# JTAG_UART.net
KiCad netlist of a schematic drawn in Altium Designer
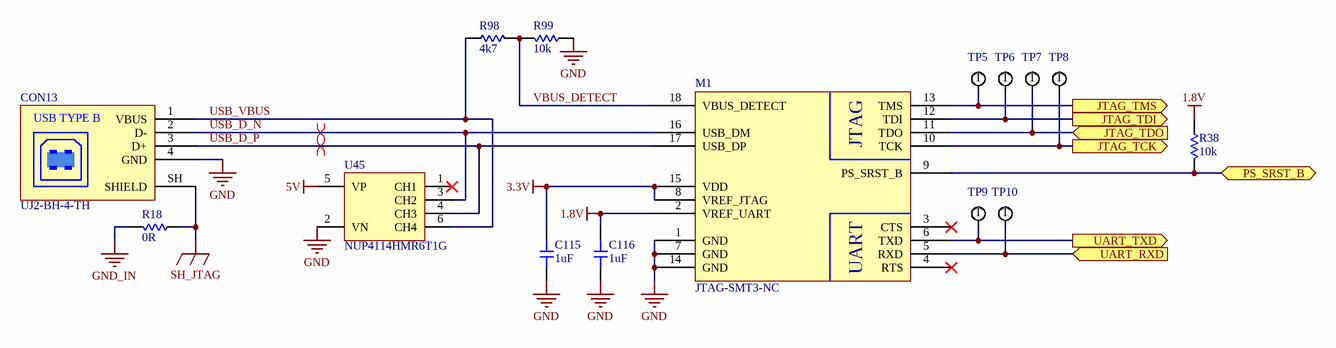
[diagram p0: JTAG_UART.SchDoc]

(export (version "E")
  (design (tool "Eeschema 10.0.6"))
  (components
    (comp (ref "C115")
      (value "1uF")
      (footprint "0603-CAP")
      (description "Capacitor")
      (libsource (lib "AMDC") (part "Capacitor"))
    )
    (comp (ref "C116")
      (value "1uF")
      (footprint "0603-CAP")
      (description "Capacitor")
      (libsource (lib "AMDC") (part "Capacitor"))
    )
    (comp (ref "CON13")
      (value "UJ2-BH-4-TH")
      (footprint "UJ2-BH-4-TH")
      (description "CONN RCPT USB2.0 TYPEB 4POS R/A")
      (libsource (lib "AMDC") (part "UJ2-BH-4-TH"))
    )
    (comp (ref "M1")
      (value "JTAG-SMT3-NC")
      (footprint "JTAG-SMT3-NC")
      (description "JTAG-SMT3-NC: SURFACE-MOUNT PROG")
      (libsource (lib "AMDC") (part "JTAG-SMT3-NC"))
    )
    (comp (ref "R18")
      (value "0R")
      (footprint "1206-RES")
      (description "Resistor")
      (libsource (lib "AMDC") (part "Resistor"))
    )
    (comp (ref "R38")
      (value "10k")
      (footprint "0603-RES")
      (description "Resistor")
      (libsource (lib "AMDC") (part "Resistor"))
    )
    (comp (ref "R98")
      (value "4k7")
      (footprint "0603-RES")
      (description "Resistor")
      (libsource (lib "AMDC") (part "Resistor"))
    )
    (comp (ref "R99")
      (value "10k")
      (footprint "0603-RES")
      (description "Resistor")
      (libsource (lib "AMDC") (part "Resistor"))
    )
    (comp (ref "TP5") (value "Test Point") (footprint "TP-125") (libsource (lib "AMDC") (part "Test Point")))
    (comp (ref "TP6") (value "Test Point") (footprint "TP-125") (libsource (lib "AMDC") (part "Test Point")))
    (comp (ref "TP7") (value "Test Point") (footprint "TP-125") (libsource (lib "AMDC") (part "Test Point")))
    (comp (ref "TP8") (value "Test Point") (footprint "TP-125") (libsource (lib "AMDC") (part "Test Point")))
    (comp (ref "TP9") (value "Test Point") (footprint "TP-125") (libsource (lib "AMDC") (part "Test Point")))
    (comp (ref "TP10") (value "Test Point") (footprint "TP-125") (libsource (lib "AMDC") (part "Test Point")))
    (comp (ref "U45")
      (value "NUP4114HMR6T1G")
      (footprint "TSOP95P280X110-6N")
      (description "TVS DIODE 5.5V 10V 6TSOP")
      (libsource (lib "AMDC") (part "NUP4114HMR6T1G"))
    )
  )
  (nets
    (net (code "1") (name "/JTAG_TCK") (class "Default")
      (node (ref "M1") (pin "10") (pinfunction "TCK_10") (pintype "passive"))
      (node (ref "TP8") (pin "1") (pinfunction "1_1") (pintype "passive"))
    )
    (net (code "2") (name "/JTAG_TDI") (class "Default")
      (node (ref "M1") (pin "12") (pinfunction "TDI_12") (pintype "passive"))
      (node (ref "TP6") (pin "1") (pinfunction "1_1") (pintype "passive"))
    )
    (net (code "3") (name "/JTAG_TDO") (class "Default")
      (node (ref "M1") (pin "11") (pinfunction "TDO_11") (pintype "passive"))
      (node (ref "TP7") (pin "1") (pinfunction "1_1") (pintype "passive"))
    )
    (net (code "4") (name "/JTAG_TMS") (class "Default")
      (node (ref "M1") (pin "13") (pinfunction "TMS_13") (pintype "passive"))
      (node (ref "TP5") (pin "1") (pinfunction "1_1") (pintype "passive"))
    )
    (net (code "5") (name "/PS_SRST_B") (class "Default")
      (node (ref "M1") (pin "9") (pinfunction "PS_SRST_B_9") (pintype "passive"))
      (node (ref "R38") (pin "2") (pinfunction "2_2") (pintype "passive"))
    )
    (net (code "6") (name "/UART_RXD") (class "Default")
      (node (ref "M1") (pin "5") (pinfunction "RXD_5") (pintype "passive"))
      (node (ref "TP10") (pin "1") (pinfunction "1_1") (pintype "passive"))
    )
    (net (code "7") (name "/UART_TXD") (class "Default")
      (node (ref "M1") (pin "6") (pinfunction "TXD_6") (pintype "passive"))
      (node (ref "TP9") (pin "1") (pinfunction "1_1") (pintype "passive"))
    )
    (net (code "8") (name "/USB_D_N") (class "Default")
      (node (ref "CON13") (pin "2") (pinfunction "D-_2") (pintype "passive"))
      (node (ref "M1") (pin "16") (pinfunction "USB_DM_16") (pintype "passive"))
      (node (ref "U45") (pin "3") (pinfunction "CH2_3") (pintype "passive"))
    )
    (net (code "9") (name "/USB_D_P") (class "Default")
      (node (ref "CON13") (pin "3") (pinfunction "D+_3") (pintype "passive"))
      (node (ref "M1") (pin "17") (pinfunction "USB_DP_17") (pintype "passive"))
      (node (ref "U45") (pin "4") (pinfunction "CH3_4") (pintype "passive"))
    )
    (net (code "10") (name "/USB_VBUS") (class "Default")
      (node (ref "CON13") (pin "1") (pinfunction "VBUS_1") (pintype "passive"))
      (node (ref "R98") (pin "1") (pinfunction "1_1") (pintype "passive"))
      (node (ref "U45") (pin "6") (pinfunction "CH4_6") (pintype "passive"))
    )
    (net (code "11") (name "/VBUS_DETECT") (class "Default")
      (node (ref "M1") (pin "18") (pinfunction "VBUS_DETECT_18") (pintype "passive"))
      (node (ref "R98") (pin "2") (pinfunction "2_2") (pintype "passive"))
      (node (ref "R99") (pin "2") (pinfunction "2_2") (pintype "passive"))
    )
    (net (code "12") (name "1.8V") (class "Default")
      (node (ref "C116") (pin "2") (pinfunction "2_2") (pintype "passive"))
      (node (ref "M1") (pin "2") (pinfunction "VREF_UART_2") (pintype "passive"))
      (node (ref "R38") (pin "1") (pinfunction "1_1") (pintype "passive"))
    )
    (net (code "13") (name "3.3V") (class "Default")
      (node (ref "C115") (pin "2") (pinfunction "2_2") (pintype "passive"))
      (node (ref "M1") (pin "15") (pinfunction "VDD_15") (pintype "passive"))
      (node (ref "M1") (pin "8") (pinfunction "VREF_JTAG_8") (pintype "passive"))
    )
    (net (code "14") (name "5V") (class "Default")
      (node (ref "U45") (pin "5") (pinfunction "VP_5") (pintype "passive"))
    )
    (net (code "15") (name "GND") (class "Default")
      (node (ref "C115") (pin "1") (pinfunction "1_1") (pintype "passive"))
      (node (ref "C116") (pin "1") (pinfunction "1_1") (pintype "passive"))
      (node (ref "CON13") (pin "4") (pinfunction "GND_4") (pintype "passive"))
      (node (ref "M1") (pin "1") (pinfunction "GND_1") (pintype "passive"))
      (node (ref "M1") (pin "14") (pinfunction "GND_14") (pintype "passive"))
      (node (ref "M1") (pin "7") (pinfunction "GND_7") (pintype "passive"))
      (node (ref "R99") (pin "1") (pinfunction "1_1") (pintype "passive"))
      (node (ref "U45") (pin "2") (pinfunction "VN_2") (pintype "passive"))
    )
    (net (code "16") (name "GND_IN") (class "Default")
      (node (ref "R18") (pin "2") (pinfunction "2_2") (pintype "passive"))
    )
    (net (code "17") (name "SH_JTAG") (class "Default")
      (node (ref "CON13") (pin "SH") (pinfunction "SHIELD_SH") (pintype "passive"))
      (node (ref "R18") (pin "1") (pinfunction "1_1") (pintype "passive"))
    )
    (net (code "18") (name "unconnected-(M1-CTS-Pad3)") (class "Default")
      (node (ref "M1") (pin "3") (pinfunction "CTS_3") (pintype "passive+no_connect"))
    )
    (net (code "19") (name "unconnected-(M1-RTS-Pad4)") (class "Default")
      (node (ref "M1") (pin "4") (pinfunction "RTS_4") (pintype "passive+no_connect"))
    )
    (net (code "20") (name "unconnected-(U45-CH1-Pad1)") (class "Default")
      (node (ref "U45") (pin "1") (pinfunction "CH1_1") (pintype "passive+no_connect"))
    )
  )
)
